# converter_board.net
KiCad netlist of a schematic drawn in EAGLE
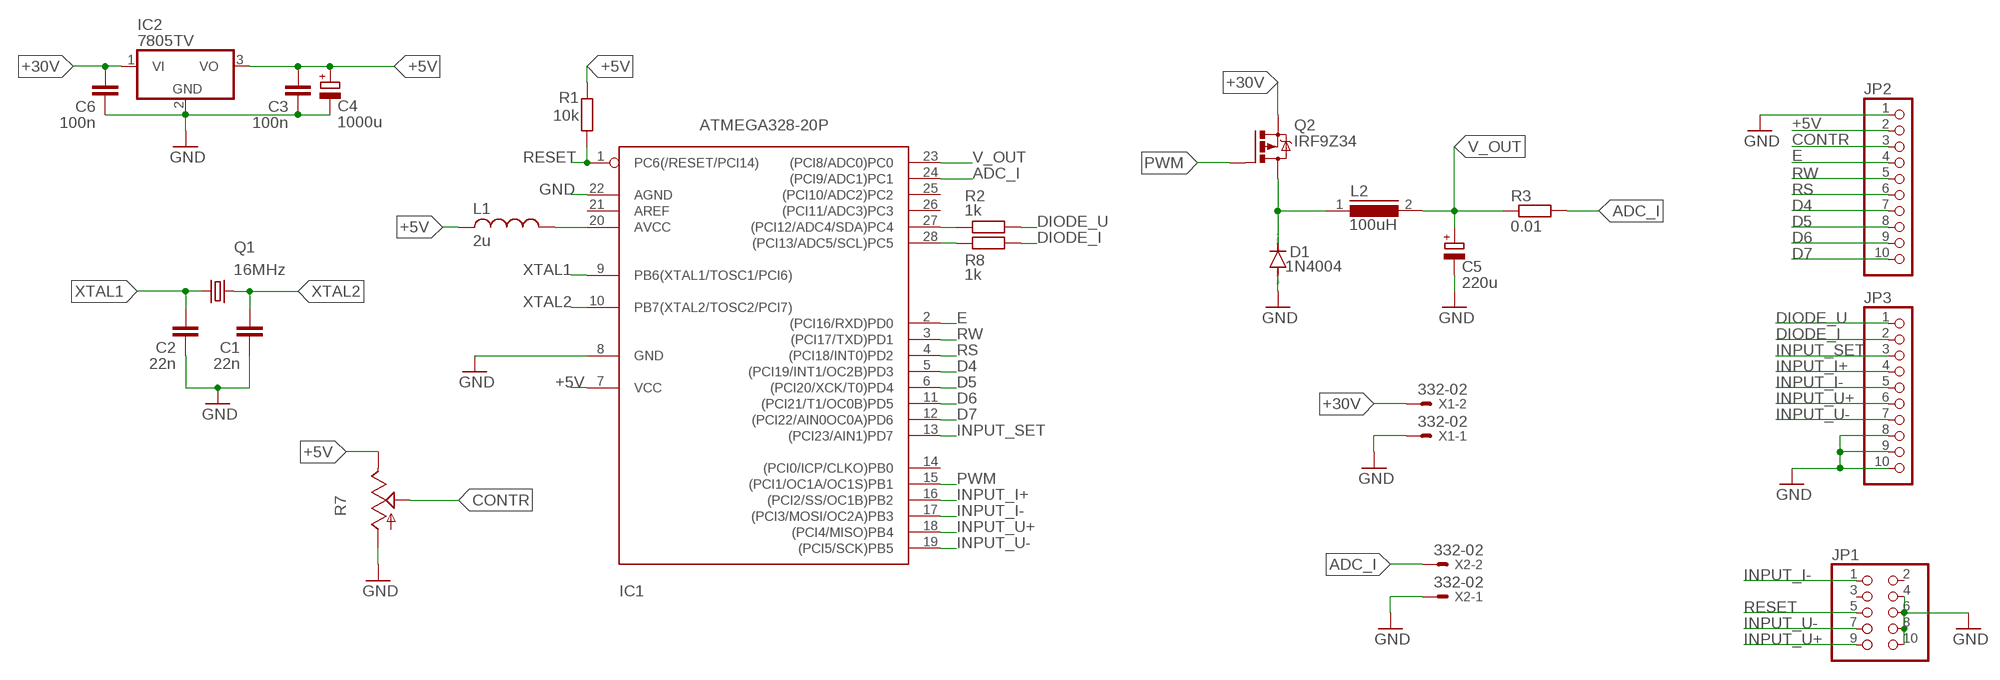
[diagram p0: schematic, sheet 1]

(export (version "E")
  (design (tool "Eeschema 10.0.6"))
  (components
    (comp (ref "C1")
      (value "22n")
      (footprint "eagle-import:C2.5-3")
      (libsource (lib "eagle-import") (part "C2,5-3"))
    )
    (comp (ref "C2")
      (value "22n")
      (footprint "eagle-import:C2.5-3")
      (libsource (lib "eagle-import") (part "C2,5-3"))
    )
    (comp (ref "C3")
      (value "100n")
      (footprint "eagle-import:C2.5-3")
      (libsource (lib "eagle-import") (part "C2,5-3"))
    )
    (comp (ref "C4")
      (value "1000u")
      (footprint "eagle-import:E2,5-7")
      (libsource (lib "eagle-import") (part "CPOL-EUE2.5-7"))
    )
    (comp (ref "C5")
      (value "220u")
      (footprint "eagle-import:E2,5-7")
      (libsource (lib "eagle-import") (part "CPOL-EUE2.5-7"))
    )
    (comp (ref "C6")
      (value "100n")
      (footprint "eagle-import:C2.5-3")
      (libsource (lib "eagle-import") (part "C2,5-3"))
    )
    (comp (ref "D1")
      (value "1N4004")
      (footprint "eagle-import:DO41-10")
      (libsource (lib "eagle-import") (part "1N4004"))
    )
    (comp (ref "IC1")
      (value "ATMEGA328-20P")
      (footprint "eagle-import:DIL28-3")
      (libsource (lib "eagle-import") (part "ATMEGA328P-20"))
    )
    (comp (ref "IC2")
      (value "7805TV")
      (footprint "eagle-import:TO220V")
      (libsource (lib "eagle-import") (part "78TV05"))
    )
    (comp (ref "JP1")
      (value "PINHD-2X5")
      (footprint "eagle-import:2X05")
      (libsource (lib "eagle-import") (part "PINHD-2X5"))
    )
    (comp (ref "JP2")
      (value "PINHD-1X10")
      (footprint "eagle-import:1X10")
      (libsource (lib "eagle-import") (part "PINHD-1X10"))
    )
    (comp (ref "JP3")
      (value "PINHD-1X10")
      (footprint "eagle-import:1X10")
      (libsource (lib "eagle-import") (part "PINHD-1X10"))
    )
    (comp (ref "L1")
      (value "2u")
      (footprint "eagle-import:0204_7")
      (libsource (lib "eagle-import") (part "L-US0204/7"))
    )
    (comp (ref "L2")
      (value "100uH")
      (footprint "eagle-import:ED26")
      (libsource (lib "eagle-import") (part "ED26"))
    )
    (comp (ref "Q1")
      (value "16MHz")
      (footprint "eagle-import:HC49_S")
      (libsource (lib "eagle-import") (part "CRYSTALHC49S"))
    )
    (comp (ref "Q2")
      (value "IRF9Z34")
      (footprint "eagle-import:TO220BH")
      (libsource (lib "eagle-import") (part "IRF4905"))
    )
    (comp (ref "R1")
      (value "10k")
      (footprint "eagle-import:0204_7")
      (libsource (lib "eagle-import") (part "resistor_348_R-EU_0204/7"))
    )
    (comp (ref "R2")
      (value "1k")
      (footprint "eagle-import:0204_7")
      (libsource (lib "eagle-import") (part "resistor_348_R-EU_0204/7"))
    )
    (comp (ref "R3")
      (value "0.01")
      (footprint "eagle-import:0207_10")
      (libsource (lib "eagle-import") (part "R-EU_0207/10"))
    )
    (comp (ref "R7")
      (value "TRIM_US-LI10")
      (footprint "eagle-import:LI10")
      (libsource (lib "eagle-import") (part "TRIM_US-LI10"))
    )
    (comp (ref "R8")
      (value "1k")
      (footprint "eagle-import:0204_7")
      (libsource (lib "eagle-import") (part "resistor_348_R-EU_0204/7"))
    )
    (comp (ref "X1")
      (value "332-02")
      (footprint "eagle-import:332-02")
      (libsource (lib "eagle-import") (part "332-02"))
    )
    (comp (ref "X2")
      (value "332-02")
      (footprint "eagle-import:332-02")
      (libsource (lib "eagle-import") (part "332-02"))
    )
  )
  (nets
    (net (code "1") (name "+5V") (class "Default")
      (node (ref "C3") (pin "2") (pinfunction "2_2") (pintype "passive"))
      (node (ref "C4") (pin "+") (pinfunction "+_+") (pintype "passive"))
      (node (ref "IC1") (pin "7") (pinfunction "VCC_7") (pintype "bidirectional"))
      (node (ref "IC2") (pin "3") (pinfunction "VO_3") (pintype "passive"))
      (node (ref "JP2") (pin "2") (pinfunction "2_2") (pintype "passive"))
      (node (ref "L1") (pin "1") (pinfunction "1_1") (pintype "passive"))
      (node (ref "R1") (pin "2") (pinfunction "2_2") (pintype "passive"))
      (node (ref "R7") (pin "E") (pinfunction "E_E") (pintype "passive"))
    )
    (net (code "2") (name "+30V") (class "Default")
      (node (ref "C6") (pin "2") (pinfunction "2_2") (pintype "passive"))
      (node (ref "IC2") (pin "1") (pinfunction "VI_1") (pintype "input"))
      (node (ref "Q2") (pin "S") (pinfunction "S_S") (pintype "passive"))
      (node (ref "X1") (pin "2") (pinfunction "S_2") (pintype "passive"))
    )
    (net (code "3") (name "/D4") (class "Default")
      (node (ref "IC1") (pin "5") (pinfunction "(PCI19/INT1/OC2B)PD3_5") (pintype "bidirectional"))
      (node (ref "JP2") (pin "7") (pinfunction "7_7") (pintype "passive"))
    )
    (net (code "4") (name "/D5") (class "Default")
      (node (ref "IC1") (pin "6") (pinfunction "(PCI20/XCK/T0)PD4_6") (pintype "bidirectional"))
      (node (ref "JP2") (pin "8") (pinfunction "8_8") (pintype "passive"))
    )
    (net (code "5") (name "/D6") (class "Default")
      (node (ref "IC1") (pin "11") (pinfunction "(PCI21/T1/OC0B)PD5_11") (pintype "bidirectional"))
      (node (ref "JP2") (pin "9") (pinfunction "9_9") (pintype "passive"))
    )
    (net (code "6") (name "/D7") (class "Default")
      (node (ref "IC1") (pin "12") (pinfunction "(PCI22/AIN0OC0A)PD6_12") (pintype "bidirectional"))
      (node (ref "JP2") (pin "10") (pinfunction "10_10") (pintype "passive"))
    )
    (net (code "7") (name "/DIODE_I") (class "Default")
      (node (ref "JP3") (pin "2") (pinfunction "2_2") (pintype "passive"))
      (node (ref "R8") (pin "1") (pinfunction "1_1") (pintype "passive"))
    )
    (net (code "8") (name "/DIODE_U") (class "Default")
      (node (ref "JP3") (pin "1") (pinfunction "1_1") (pintype "passive"))
      (node (ref "R2") (pin "1") (pinfunction "1_1") (pintype "passive"))
    )
    (net (code "9") (name "/E") (class "Default")
      (node (ref "IC1") (pin "2") (pinfunction "(PCI16/RXD)PD0_2") (pintype "bidirectional"))
      (node (ref "JP2") (pin "4") (pinfunction "4_4") (pintype "passive"))
    )
    (net (code "10") (name "/INPUT_I+") (class "Default")
      (node (ref "IC1") (pin "16") (pinfunction "(PCI2/SS/OC1B)PB2_16") (pintype "bidirectional"))
      (node (ref "JP3") (pin "4") (pinfunction "4_4") (pintype "passive"))
    )
    (net (code "11") (name "/INPUT_I-") (class "Default")
      (node (ref "IC1") (pin "17") (pinfunction "(PCI3/MOSI/OC2A)PB3_17") (pintype "bidirectional"))
      (node (ref "JP1") (pin "1") (pinfunction "1_1") (pintype "passive"))
      (node (ref "JP3") (pin "5") (pinfunction "5_5") (pintype "passive"))
    )
    (net (code "12") (name "/INPUT_SET") (class "Default")
      (node (ref "IC1") (pin "13") (pinfunction "(PCI23/AIN1)PD7_13") (pintype "bidirectional"))
      (node (ref "JP3") (pin "3") (pinfunction "3_3") (pintype "passive"))
    )
    (net (code "13") (name "/INPUT_U+") (class "Default")
      (node (ref "IC1") (pin "18") (pinfunction "(PCI4/MISO)PB4_18") (pintype "bidirectional"))
      (node (ref "JP1") (pin "9") (pinfunction "9_9") (pintype "passive"))
      (node (ref "JP3") (pin "6") (pinfunction "6_6") (pintype "passive"))
    )
    (net (code "14") (name "/INPUT_U-") (class "Default")
      (node (ref "IC1") (pin "19") (pinfunction "(PCI5/SCK)PB5_19") (pintype "bidirectional"))
      (node (ref "JP1") (pin "7") (pinfunction "7_7") (pintype "passive"))
      (node (ref "JP3") (pin "7") (pinfunction "7_7") (pintype "passive"))
    )
    (net (code "15") (name "/RESET") (class "Default")
      (node (ref "IC1") (pin "1") (pinfunction "PC6(/RESET/PCI14)_1") (pintype "bidirectional"))
      (node (ref "JP1") (pin "5") (pinfunction "5_5") (pintype "passive"))
      (node (ref "R1") (pin "1") (pinfunction "1_1") (pintype "passive"))
    )
    (net (code "16") (name "/RS") (class "Default")
      (node (ref "IC1") (pin "4") (pinfunction "(PCI18/INT0)PD2_4") (pintype "bidirectional"))
      (node (ref "JP2") (pin "6") (pinfunction "6_6") (pintype "passive"))
    )
    (net (code "17") (name "/RW") (class "Default")
      (node (ref "IC1") (pin "3") (pinfunction "(PCI17/TXD)PD1_3") (pintype "bidirectional"))
      (node (ref "JP2") (pin "5") (pinfunction "5_5") (pintype "passive"))
    )
    (net (code "18") (name "ADC_I") (class "Default")
      (node (ref "IC1") (pin "24") (pinfunction "(PCI9/ADC1)PC1_24") (pintype "bidirectional"))
      (node (ref "R3") (pin "2") (pinfunction "2_2") (pintype "passive"))
      (node (ref "X2") (pin "2") (pinfunction "S_2") (pintype "passive"))
    )
    (net (code "19") (name "CONTR") (class "Default")
      (node (ref "JP2") (pin "3") (pinfunction "3_3") (pintype "passive"))
      (node (ref "R7") (pin "S") (pinfunction "S_S") (pintype "passive"))
    )
    (net (code "20") (name "GND") (class "Default")
      (node (ref "C1") (pin "1") (pinfunction "1_1") (pintype "passive"))
      (node (ref "C2") (pin "1") (pinfunction "1_1") (pintype "passive"))
      (node (ref "C3") (pin "1") (pinfunction "1_1") (pintype "passive"))
      (node (ref "C4") (pin "-") (pinfunction "-_-") (pintype "passive"))
      (node (ref "C5") (pin "-") (pinfunction "-_-") (pintype "passive"))
      (node (ref "C6") (pin "1") (pinfunction "1_1") (pintype "passive"))
      (node (ref "D1") (pin "A") (pinfunction "A_A") (pintype "passive"))
      (node (ref "IC1") (pin "22") (pinfunction "AGND_22") (pintype "bidirectional"))
      (node (ref "IC1") (pin "8") (pinfunction "GND_8") (pintype "bidirectional"))
      (node (ref "IC2") (pin "2") (pinfunction "GND_2") (pintype "passive"))
      (node (ref "JP1") (pin "10") (pinfunction "10_10") (pintype "passive"))
      (node (ref "JP1") (pin "4") (pinfunction "4_4") (pintype "passive"))
      (node (ref "JP1") (pin "6") (pinfunction "6_6") (pintype "passive"))
      (node (ref "JP1") (pin "8") (pinfunction "8_8") (pintype "passive"))
      (node (ref "JP2") (pin "1") (pinfunction "1_1") (pintype "passive"))
      (node (ref "JP3") (pin "10") (pinfunction "10_10") (pintype "passive"))
      (node (ref "JP3") (pin "8") (pinfunction "8_8") (pintype "passive"))
      (node (ref "JP3") (pin "9") (pinfunction "9_9") (pintype "passive"))
      (node (ref "R7") (pin "A") (pinfunction "A_A") (pintype "passive"))
      (node (ref "X1") (pin "1") (pinfunction "S_1") (pintype "passive"))
      (node (ref "X2") (pin "1") (pinfunction "S_1") (pintype "passive"))
    )
    (net (code "21") (name "Net-(D1-PadC)") (class "Default")
      (node (ref "D1") (pin "C") (pinfunction "C_C") (pintype "passive"))
      (node (ref "L2") (pin "1") (pinfunction "1_1") (pintype "passive"))
      (node (ref "Q2") (pin "D") (pinfunction "D_D") (pintype "passive"))
    )
    (net (code "22") (name "Net-(IC1-(PCI12{slash}ADC4{slash}SDA)PC4)") (class "Default")
      (node (ref "IC1") (pin "27") (pinfunction "(PCI12/ADC4/SDA)PC4_27") (pintype "bidirectional"))
      (node (ref "R2") (pin "2") (pinfunction "2_2") (pintype "passive"))
    )
    (net (code "23") (name "Net-(IC1-(PCI13{slash}ADC5{slash}SCL)PC5)") (class "Default")
      (node (ref "IC1") (pin "28") (pinfunction "(PCI13/ADC5/SCL)PC5_28") (pintype "bidirectional"))
      (node (ref "R8") (pin "2") (pinfunction "2_2") (pintype "passive"))
    )
    (net (code "24") (name "Net-(IC1-AVCC)") (class "Default")
      (node (ref "IC1") (pin "20") (pinfunction "AVCC_20") (pintype "bidirectional"))
      (node (ref "L1") (pin "2") (pinfunction "2_2") (pintype "passive"))
    )
    (net (code "25") (name "PWM") (class "Default")
      (node (ref "IC1") (pin "15") (pinfunction "(PCI1/OC1A/OC1S)PB1_15") (pintype "bidirectional"))
      (node (ref "Q2") (pin "G") (pinfunction "G_G") (pintype "passive"))
    )
    (net (code "26") (name "V_OUT") (class "Default")
      (node (ref "C5") (pin "+") (pinfunction "+_+") (pintype "passive"))
      (node (ref "IC1") (pin "23") (pinfunction "(PCI8/ADC0)PC0_23") (pintype "bidirectional"))
      (node (ref "L2") (pin "2") (pinfunction "2_2") (pintype "passive"))
      (node (ref "R3") (pin "1") (pinfunction "1_1") (pintype "passive"))
    )
    (net (code "27") (name "XTAL1") (class "Default")
      (node (ref "C2") (pin "2") (pinfunction "2_2") (pintype "passive"))
      (node (ref "IC1") (pin "9") (pinfunction "PB6(XTAL1/TOSC1/PCI6)_9") (pintype "bidirectional"))
      (node (ref "Q1") (pin "2") (pinfunction "2_2") (pintype "passive"))
    )
    (net (code "28") (name "XTAL2") (class "Default")
      (node (ref "C1") (pin "2") (pinfunction "2_2") (pintype "passive"))
      (node (ref "IC1") (pin "10") (pinfunction "PB7(XTAL2/TOSC2/PCI7)_10") (pintype "bidirectional"))
      (node (ref "Q1") (pin "1") (pinfunction "1_1") (pintype "passive"))
    )
    (net (code "29") (name "unconnected-(IC1-(PCI0{slash}ICP{slash}CLKO)PB0-Pad14)") (class "Default")
      (node (ref "IC1") (pin "14") (pinfunction "(PCI0/ICP/CLKO)PB0_14") (pintype "bidirectional"))
    )
    (net (code "30") (name "unconnected-(IC1-(PCI10{slash}ADC2)PC2-Pad25)") (class "Default")
      (node (ref "IC1") (pin "25") (pinfunction "(PCI10/ADC2)PC2_25") (pintype "bidirectional"))
    )
    (net (code "31") (name "unconnected-(IC1-(PCI11{slash}ADC3)PC3-Pad26)") (class "Default")
      (node (ref "IC1") (pin "26") (pinfunction "(PCI11/ADC3)PC3_26") (pintype "bidirectional"))
    )
    (net (code "32") (name "unconnected-(IC1-AREF-Pad21)") (class "Default")
      (node (ref "IC1") (pin "21") (pinfunction "AREF_21") (pintype "bidirectional"))
    )
    (net (code "33") (name "unconnected-(JP1-Pad2)") (class "Default")
      (node (ref "JP1") (pin "2") (pinfunction "2_2") (pintype "passive"))
    )
    (net (code "34") (name "unconnected-(JP1-Pad3)") (class "Default")
      (node (ref "JP1") (pin "3") (pinfunction "3_3") (pintype "passive"))
    )
  )
)
